# Audio.net
KiCad netlist of a schematic drawn in Altium Designer
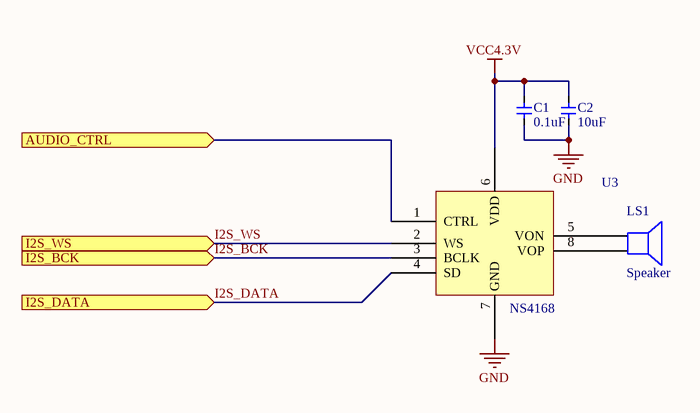
[diagram p0: Audio.SchDoc]

(export (version "E")
  (design (tool "Eeschema 10.0.6"))
  (components
    (comp (ref "C1")
      (value "0.1uF")
      (footprint "PCB_PassiveCap:CAP_0603")
      (description "Capacitor")
      (fields (field (name "Comment") "Cap_0603"))
      (libsource (lib "SCH_Passive") (part "Cap_0603"))
    )
    (comp (ref "C2")
      (value "10uF")
      (footprint "PCB_PassiveCap:CAP_0603")
      (description "Capacitor")
      (fields (field (name "Comment") "Cap_0603"))
      (libsource (lib "SCH_Passive") (part "Cap_0603"))
    )
    (comp (ref "LS1")
      (value "Speaker")
      (footprint "PIN2")
      (description "Loudspeaker")
      (fields (field (name "PUBLISHER") "Altium Limited"))
      (libsource (lib "Miscellaneous Devices") (part "Speaker"))
    )
    (comp (ref "U3")
      (value "NS4168")
      (footprint "SOP_E150_8")
      (description "D Class Audio Amp with I2S input")
      (libsource (lib "SCH_IntegratedCircuit") (part "NS4168"))
    )
  )
  (nets
    (net (code "1") (name "/AUDIO_CTRL") (class "Default")
      (node (ref "U3") (pin "1") (pinfunction "CTRL_1") (pintype "passive"))
    )
    (net (code "2") (name "/I2S_BCK") (class "Default")
      (node (ref "U3") (pin "3") (pinfunction "BCLK_3") (pintype "passive"))
    )
    (net (code "3") (name "/I2S_DATA") (class "Default")
      (node (ref "U3") (pin "4") (pinfunction "SD_4") (pintype "passive"))
    )
    (net (code "4") (name "/I2S_WS") (class "Default")
      (node (ref "U3") (pin "2") (pinfunction "WS_2") (pintype "passive"))
    )
    (net (code "5") (name "GND") (class "Default")
      (node (ref "C1") (pin "1") (pinfunction "1_1") (pintype "passive"))
      (node (ref "C2") (pin "1") (pinfunction "1_1") (pintype "passive"))
      (node (ref "U3") (pin "7") (pinfunction "GND_7") (pintype "passive"))
    )
    (net (code "6") (name "Net-(U3-VON)") (class "Default")
      (node (ref "LS1") (pin "1") (pinfunction "1_1") (pintype "passive"))
      (node (ref "U3") (pin "5") (pinfunction "VON_5") (pintype "passive"))
    )
    (net (code "7") (name "Net-(U3-VOP)") (class "Default")
      (node (ref "LS1") (pin "2") (pinfunction "2_2") (pintype "passive"))
      (node (ref "U3") (pin "8") (pinfunction "VOP_8") (pintype "passive"))
    )
    (net (code "8") (name "VCC4.3V") (class "Default")
      (node (ref "C1") (pin "2") (pinfunction "2_2") (pintype "passive"))
      (node (ref "C2") (pin "2") (pinfunction "2_2") (pintype "passive"))
      (node (ref "U3") (pin "6") (pinfunction "VDD_6") (pintype "passive"))
    )
  )
)
